# Carte_moteur.net
KiCad netlist of a schematic drawn in EAGLE
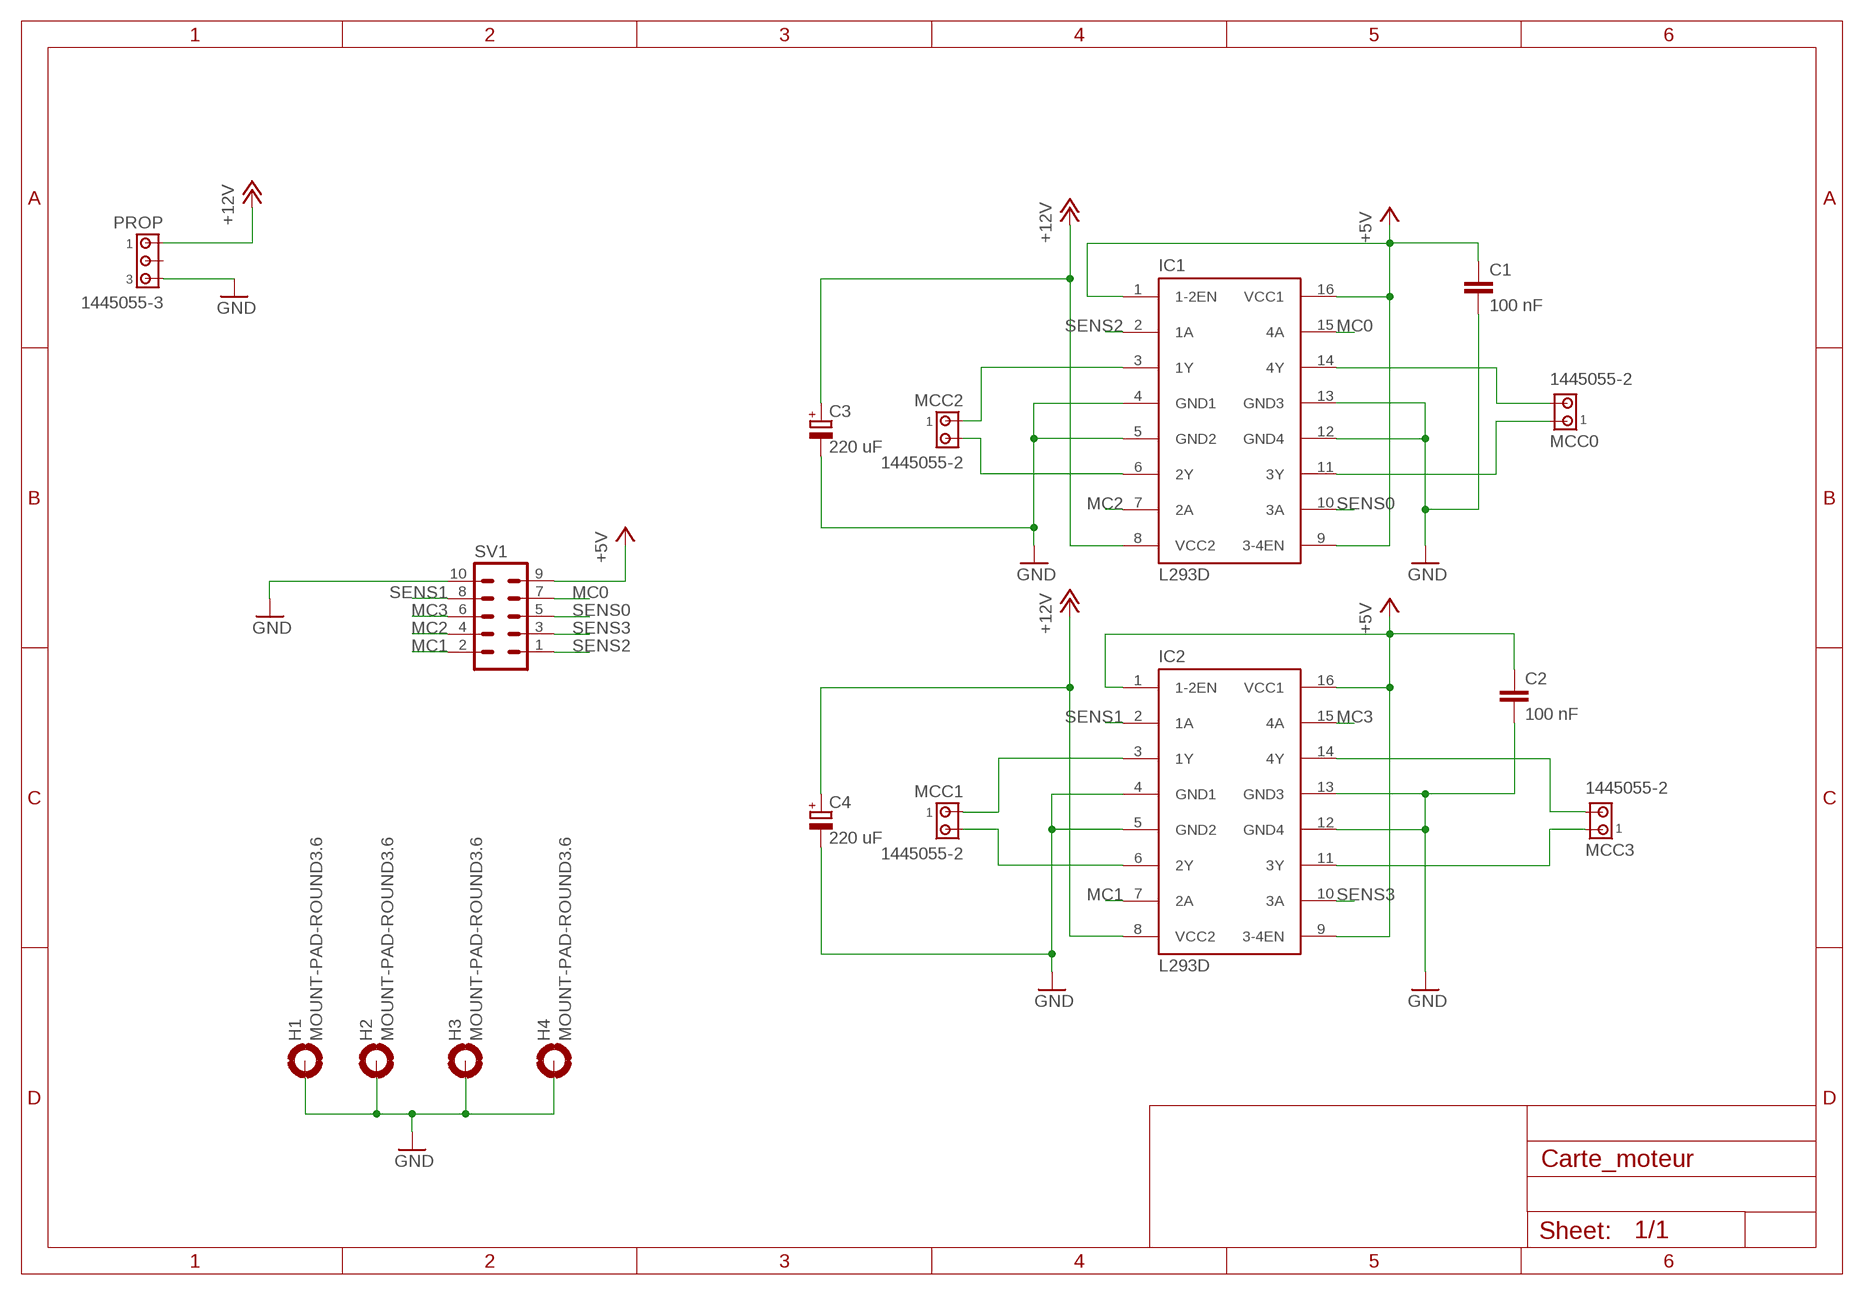
[diagram p0: schematic, sheet 1]

(export (version "E")
  (design (tool "Eeschema 10.0.6"))
  (components
    (comp (ref "C1")
      (value "100 nF")
      (footprint "eagle-import:C0805")
      (libsource (lib "eagle-import") (part "C-EUC0805"))
    )
    (comp (ref "C2")
      (value "100 nF")
      (footprint "eagle-import:C0805")
      (libsource (lib "eagle-import") (part "C-EUC0805"))
    )
    (comp (ref "C3")
      (value "220 uF")
      (footprint "eagle-import:PANASONIC_G")
      (libsource (lib "eagle-import") (part "CPOL-EUG"))
    )
    (comp (ref "C4")
      (value "220 uF")
      (footprint "eagle-import:PANASONIC_G")
      (libsource (lib "eagle-import") (part "CPOL-EUG"))
    )
    (comp (ref "H1")
      (value "MOUNT-PAD-ROUND3.6")
      (footprint "eagle-import:3,6-PAD")
      (libsource (lib "eagle-import") (part "MOUNT-PAD-ROUND3.6"))
    )
    (comp (ref "H2")
      (value "MOUNT-PAD-ROUND3.6")
      (footprint "eagle-import:3,6-PAD")
      (libsource (lib "eagle-import") (part "MOUNT-PAD-ROUND3.6"))
    )
    (comp (ref "H3")
      (value "MOUNT-PAD-ROUND3.6")
      (footprint "eagle-import:3,6-PAD")
      (libsource (lib "eagle-import") (part "MOUNT-PAD-ROUND3.6"))
    )
    (comp (ref "H4")
      (value "MOUNT-PAD-ROUND3.6")
      (footprint "eagle-import:3,6-PAD")
      (libsource (lib "eagle-import") (part "MOUNT-PAD-ROUND3.6"))
    )
    (comp (ref "IC1")
      (value "L293D")
      (footprint "eagle-import:DIL16")
      (libsource (lib "eagle-import") (part "L293D"))
    )
    (comp (ref "IC2")
      (value "L293D")
      (footprint "eagle-import:DIL16")
      (libsource (lib "eagle-import") (part "L293D"))
    )
    (comp (ref "MCC0")
      (value "1445055-2")
      (footprint "eagle-import:1445055-2")
      (libsource (lib "eagle-import") (part "1445055-2"))
    )
    (comp (ref "MCC1")
      (value "1445055-2")
      (footprint "eagle-import:1445055-2")
      (libsource (lib "eagle-import") (part "1445055-2"))
    )
    (comp (ref "MCC2")
      (value "1445055-2")
      (footprint "eagle-import:1445055-2")
      (libsource (lib "eagle-import") (part "1445055-2"))
    )
    (comp (ref "MCC3")
      (value "1445055-2")
      (footprint "eagle-import:1445055-2")
      (libsource (lib "eagle-import") (part "1445055-2"))
    )
    (comp (ref "PROP")
      (value "1445055-3")
      (footprint "eagle-import:1445055-3")
      (libsource (lib "eagle-import") (part "1445055-3"))
    )
    (comp (ref "SV1")
      (value "ML10")
      (footprint "eagle-import:ML10")
      (libsource (lib "eagle-import") (part "ML10"))
    )
  )
  (nets
    (net (code "1") (name "+5V") (class "Default")
      (node (ref "C1") (pin "1") (pinfunction "1_1") (pintype "passive"))
      (node (ref "C2") (pin "1") (pinfunction "1_1") (pintype "passive"))
      (node (ref "IC1") (pin "1") (pinfunction "1-2EN_1") (pintype "input"))
      (node (ref "IC1") (pin "16") (pinfunction "VCC1_16") (pintype "power_in"))
      (node (ref "IC1") (pin "9") (pinfunction "3-4EN_9") (pintype "input"))
      (node (ref "IC2") (pin "1") (pinfunction "1-2EN_1") (pintype "input"))
      (node (ref "IC2") (pin "16") (pinfunction "VCC1_16") (pintype "power_in"))
      (node (ref "IC2") (pin "9") (pinfunction "3-4EN_9") (pintype "input"))
      (node (ref "SV1") (pin "9") (pinfunction "9_9") (pintype "passive"))
    )
    (net (code "2") (name "+12V") (class "Default")
      (node (ref "C3") (pin "+") (pinfunction "+_+") (pintype "passive"))
      (node (ref "C4") (pin "+") (pinfunction "+_+") (pintype "passive"))
      (node (ref "IC1") (pin "8") (pinfunction "VCC2_8") (pintype "power_in"))
      (node (ref "IC2") (pin "8") (pinfunction "VCC2_8") (pintype "power_in"))
      (node (ref "PROP") (pin "1") (pinfunction "1_1") (pintype "passive"))
    )
    (net (code "3") (name "/MC0") (class "Default")
      (node (ref "IC1") (pin "15") (pinfunction "4A_15") (pintype "input"))
      (node (ref "SV1") (pin "7") (pinfunction "7_7") (pintype "passive"))
    )
    (net (code "4") (name "/MC1") (class "Default")
      (node (ref "IC2") (pin "7") (pinfunction "2A_7") (pintype "input"))
      (node (ref "SV1") (pin "2") (pinfunction "2_2") (pintype "passive"))
    )
    (net (code "5") (name "/MC2") (class "Default")
      (node (ref "IC1") (pin "7") (pinfunction "2A_7") (pintype "input"))
      (node (ref "SV1") (pin "4") (pinfunction "4_4") (pintype "passive"))
    )
    (net (code "6") (name "/MC3") (class "Default")
      (node (ref "IC2") (pin "15") (pinfunction "4A_15") (pintype "input"))
      (node (ref "SV1") (pin "6") (pinfunction "6_6") (pintype "passive"))
    )
    (net (code "7") (name "/SENS0") (class "Default")
      (node (ref "IC1") (pin "10") (pinfunction "3A_10") (pintype "input"))
      (node (ref "SV1") (pin "5") (pinfunction "5_5") (pintype "passive"))
    )
    (net (code "8") (name "/SENS1") (class "Default")
      (node (ref "IC2") (pin "2") (pinfunction "1A_2") (pintype "input"))
      (node (ref "SV1") (pin "8") (pinfunction "8_8") (pintype "passive"))
    )
    (net (code "9") (name "/SENS2") (class "Default")
      (node (ref "IC1") (pin "2") (pinfunction "1A_2") (pintype "input"))
      (node (ref "SV1") (pin "1") (pinfunction "1_1") (pintype "passive"))
    )
    (net (code "10") (name "/SENS3") (class "Default")
      (node (ref "IC2") (pin "10") (pinfunction "3A_10") (pintype "input"))
      (node (ref "SV1") (pin "3") (pinfunction "3_3") (pintype "passive"))
    )
    (net (code "11") (name "GND") (class "Default")
      (node (ref "C1") (pin "2") (pinfunction "2_2") (pintype "passive"))
      (node (ref "C2") (pin "2") (pinfunction "2_2") (pintype "passive"))
      (node (ref "C3") (pin "-") (pinfunction "-_-") (pintype "passive"))
      (node (ref "C4") (pin "-") (pinfunction "-_-") (pintype "passive"))
      (node (ref "H1") (pin "B3,6") (pinfunction "MOUNT_B3,6") (pintype "passive"))
      (node (ref "H2") (pin "B3,6") (pinfunction "MOUNT_B3,6") (pintype "passive"))
      (node (ref "H3") (pin "B3,6") (pinfunction "MOUNT_B3,6") (pintype "passive"))
      (node (ref "H4") (pin "B3,6") (pinfunction "MOUNT_B3,6") (pintype "passive"))
      (node (ref "IC1") (pin "12") (pinfunction "GND4_12") (pintype "power_in"))
      (node (ref "IC1") (pin "13") (pinfunction "GND3_13") (pintype "power_in"))
      (node (ref "IC1") (pin "4") (pinfunction "GND1_4") (pintype "power_in"))
      (node (ref "IC1") (pin "5") (pinfunction "GND2_5") (pintype "power_in"))
      (node (ref "IC2") (pin "12") (pinfunction "GND4_12") (pintype "power_in"))
      (node (ref "IC2") (pin "13") (pinfunction "GND3_13") (pintype "power_in"))
      (node (ref "IC2") (pin "4") (pinfunction "GND1_4") (pintype "power_in"))
      (node (ref "IC2") (pin "5") (pinfunction "GND2_5") (pintype "power_in"))
      (node (ref "PROP") (pin "3") (pinfunction "3_3") (pintype "passive"))
      (node (ref "SV1") (pin "10") (pinfunction "10_10") (pintype "passive"))
    )
    (net (code "12") (name "Net-(IC1-1Y)") (class "Default")
      (node (ref "IC1") (pin "3") (pinfunction "1Y_3") (pintype "output"))
      (node (ref "MCC2") (pin "1") (pinfunction "1_1") (pintype "passive"))
    )
    (net (code "13") (name "Net-(IC1-2Y)") (class "Default")
      (node (ref "IC1") (pin "6") (pinfunction "2Y_6") (pintype "output"))
      (node (ref "MCC2") (pin "2") (pinfunction "2_2") (pintype "passive"))
    )
    (net (code "14") (name "Net-(IC1-3Y)") (class "Default")
      (node (ref "IC1") (pin "11") (pinfunction "3Y_11") (pintype "output"))
      (node (ref "MCC0") (pin "1") (pinfunction "1_1") (pintype "passive"))
    )
    (net (code "15") (name "Net-(IC1-4Y)") (class "Default")
      (node (ref "IC1") (pin "14") (pinfunction "4Y_14") (pintype "output"))
      (node (ref "MCC0") (pin "2") (pinfunction "2_2") (pintype "passive"))
    )
    (net (code "16") (name "Net-(IC2-1Y)") (class "Default")
      (node (ref "IC2") (pin "3") (pinfunction "1Y_3") (pintype "output"))
      (node (ref "MCC1") (pin "1") (pinfunction "1_1") (pintype "passive"))
    )
    (net (code "17") (name "Net-(IC2-2Y)") (class "Default")
      (node (ref "IC2") (pin "6") (pinfunction "2Y_6") (pintype "output"))
      (node (ref "MCC1") (pin "2") (pinfunction "2_2") (pintype "passive"))
    )
    (net (code "18") (name "Net-(IC2-3Y)") (class "Default")
      (node (ref "IC2") (pin "11") (pinfunction "3Y_11") (pintype "output"))
      (node (ref "MCC3") (pin "1") (pinfunction "1_1") (pintype "passive"))
    )
    (net (code "19") (name "Net-(IC2-4Y)") (class "Default")
      (node (ref "IC2") (pin "14") (pinfunction "4Y_14") (pintype "output"))
      (node (ref "MCC3") (pin "2") (pinfunction "2_2") (pintype "passive"))
    )
    (net (code "20") (name "unconnected-(PROP-Pad2)") (class "Default")
      (node (ref "PROP") (pin "2") (pinfunction "2_2") (pintype "passive"))
    )
  )
)
